# Sinaliza_o_Alimenta_o___Reset.net
KiCad netlist of a schematic drawn in Altium Designer
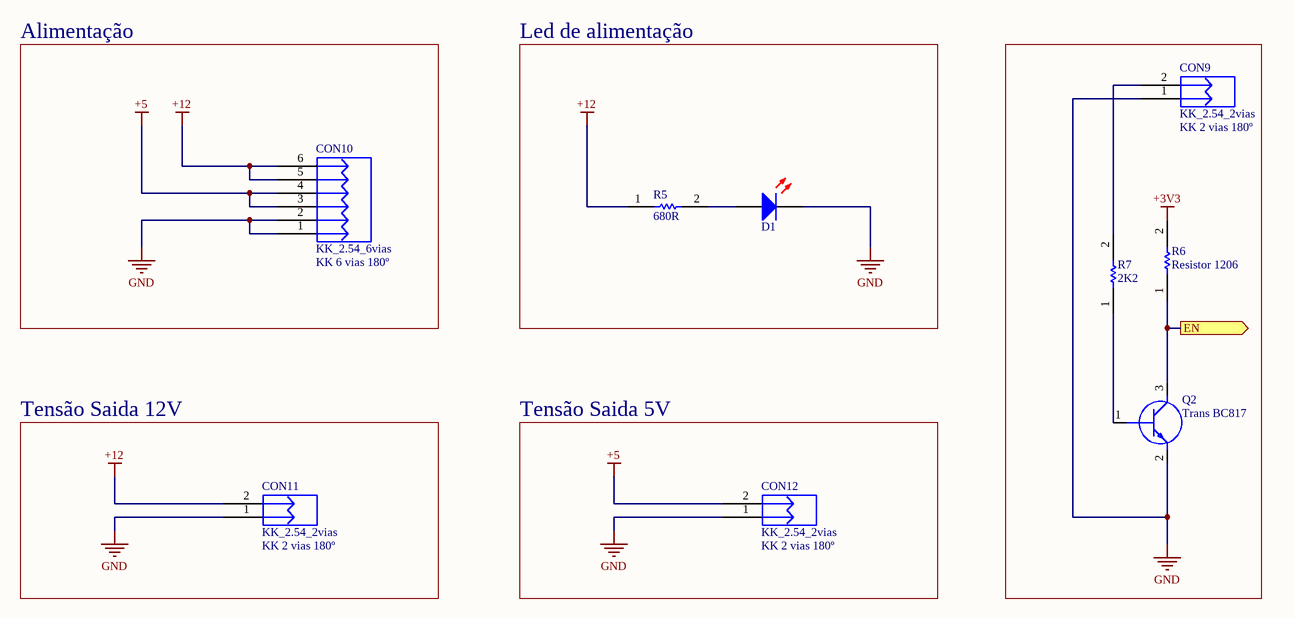
[diagram p0: Sinalização_Alimentação_&_Reset.SchDoc]

(export (version "E")
  (design (tool "Eeschema 10.0.6"))
  (components
    (comp (ref "CON9")
      (value "KK_2.54_2vias")
      (footprint "KK_2VIAS_180º")
      (description "Conector KK 2.54mm 2 vias")
      (fields (field (name "VALOR") "KK 2 vias 180º"))
      (libsource (lib "Sinalização_Official") (part "KK_2.54_2vias"))
    )
    (comp (ref "CON10")
      (value "KK_2.54_6vias")
      (footprint "KK_6vias_180°")
      (description "Conector KK 2.54mm 6 vias")
      (fields (field (name "VALOR") "KK 6 vias 180º"))
      (libsource (lib "Sinalização_Official") (part "KK_2.54_6vias"))
    )
    (comp (ref "CON11")
      (value "KK_2.54_2vias")
      (footprint "KK_2VIAS_180º")
      (description "Conector KK 2.54mm 2 vias")
      (fields (field (name "VALOR") "KK 2 vias 180º"))
      (libsource (lib "Sinalização_Official") (part "KK_2.54_2vias"))
    )
    (comp (ref "CON12")
      (value "KK_2.54_2vias")
      (footprint "KK_2VIAS_180º")
      (description "Conector KK 2.54mm 2 vias")
      (fields (field (name "VALOR") "KK 2 vias 180º"))
      (libsource (lib "Sinalização_Official") (part "KK_2.54_2vias"))
    )
    (comp (ref "D1")
      (value "LED 3MM RED")
      (footprint "LED RED")
      (fields (field (name "MANUFACTURER") "Paralight") (field (name "MANUFACTURER PART NUMBER") "IMP585"))
      (libsource (lib "Sinalização_Official") (part "LED 3MM RED"))
    )
    (comp (ref "Q2")
      (value "Trans BC817")
      (footprint "SamacSys:SOT96P240X110-3N")
      (description "Transistor BJT NPN BC817-25-7-F")
      (fields
        (field (name "MANUFACTURER_PART_NUMBER") "BC817-25-7-F")
        (field (name "MOUSER PART NUMBER") "621-BC817-25-7-F")
      )
      (libsource (lib "Sinalização_Official") (part "Trans BC817"))
    )
    (comp (ref "R5")
      (value "680R")
      (footprint "SamacSys:RESC3216X60N")
      (description "Resistor")
      (fields
        (field (name "MANUFACTURER_PART_NUMBER") "CRCW12064K70FKEA")
        (field (name "MOUSER PART NUMBER") "71-CRCW1206-4.7K-E3")
      )
      (libsource (lib "Sinalização_Official") (part "Resistor 1206"))
    )
    (comp (ref "R6")
      (value "Resistor 1206")
      (footprint "SamacSys:RESC3216X60N")
      (description "Resistor")
      (fields
        (field (name "MANUFACTURER_PART_NUMBER") "CRCW12064K70FKEA")
        (field (name "MOUSER PART NUMBER") "71-CRCW1206-4.7K-E3")
      )
      (libsource (lib "Sinalização_Official") (part "Resistor 1206"))
    )
    (comp (ref "R7")
      (value "2K2")
      (footprint "SamacSys:RESC3216X60N")
      (description "Resistor")
      (fields
        (field (name "MANUFACTURER_PART_NUMBER") "CRCW12064K70FKEA")
        (field (name "MOUSER PART NUMBER") "71-CRCW1206-4.7K-E3")
      )
      (libsource (lib "Sinalização_Official") (part "Resistor 1206"))
    )
  )
  (nets
    (net (code "1") (name "+3V3") (class "Default")
      (node (ref "R6") (pin "2") (pinfunction "2_2") (pintype "passive"))
    )
    (net (code "2") (name "+5") (class "Default")
      (node (ref "CON10") (pin "3") (pintype "passive"))
      (node (ref "CON10") (pin "4") (pintype "passive"))
      (node (ref "CON12") (pin "2") (pintype "passive"))
    )
    (net (code "3") (name "+12") (class "Default")
      (node (ref "CON10") (pin "5") (pintype "passive"))
      (node (ref "CON10") (pin "6") (pintype "passive"))
      (node (ref "CON11") (pin "2") (pintype "passive"))
      (node (ref "R5") (pin "1") (pinfunction "1_1") (pintype "passive"))
    )
    (net (code "4") (name "/EN") (class "Default")
      (node (ref "Q2") (pin "3") (pinfunction "C_3") (pintype "passive"))
      (node (ref "R6") (pin "1") (pinfunction "1_1") (pintype "passive"))
    )
    (net (code "5") (name "GND") (class "Default")
      (node (ref "CON10") (pin "1") (pintype "passive"))
      (node (ref "CON10") (pin "2") (pintype "passive"))
      (node (ref "CON11") (pin "1") (pintype "passive"))
      (node (ref "CON12") (pin "1") (pintype "passive"))
      (node (ref "CON9") (pin "1") (pintype "passive"))
      (node (ref "D1") (pin "2") (pinfunction "K_2") (pintype "passive"))
      (node (ref "Q2") (pin "2") (pinfunction "E_2") (pintype "passive"))
    )
    (net (code "6") (name "Net-(CON9-Pad2)") (class "Default")
      (node (ref "CON9") (pin "2") (pintype "passive"))
      (node (ref "R7") (pin "2") (pinfunction "2_2") (pintype "passive"))
    )
    (net (code "7") (name "Net-(D1-A)") (class "Default")
      (node (ref "D1") (pin "1") (pinfunction "A_1") (pintype "passive"))
      (node (ref "R5") (pin "2") (pinfunction "2_2") (pintype "passive"))
    )
    (net (code "8") (name "Net-(Q2-B)") (class "Default")
      (node (ref "Q2") (pin "1") (pinfunction "B_1") (pintype "passive"))
      (node (ref "R7") (pin "1") (pinfunction "1_1") (pintype "passive"))
    )
  )
)
